# D2D-BOTTOM.net
KiCad netlist of a schematic drawn in EAGLE
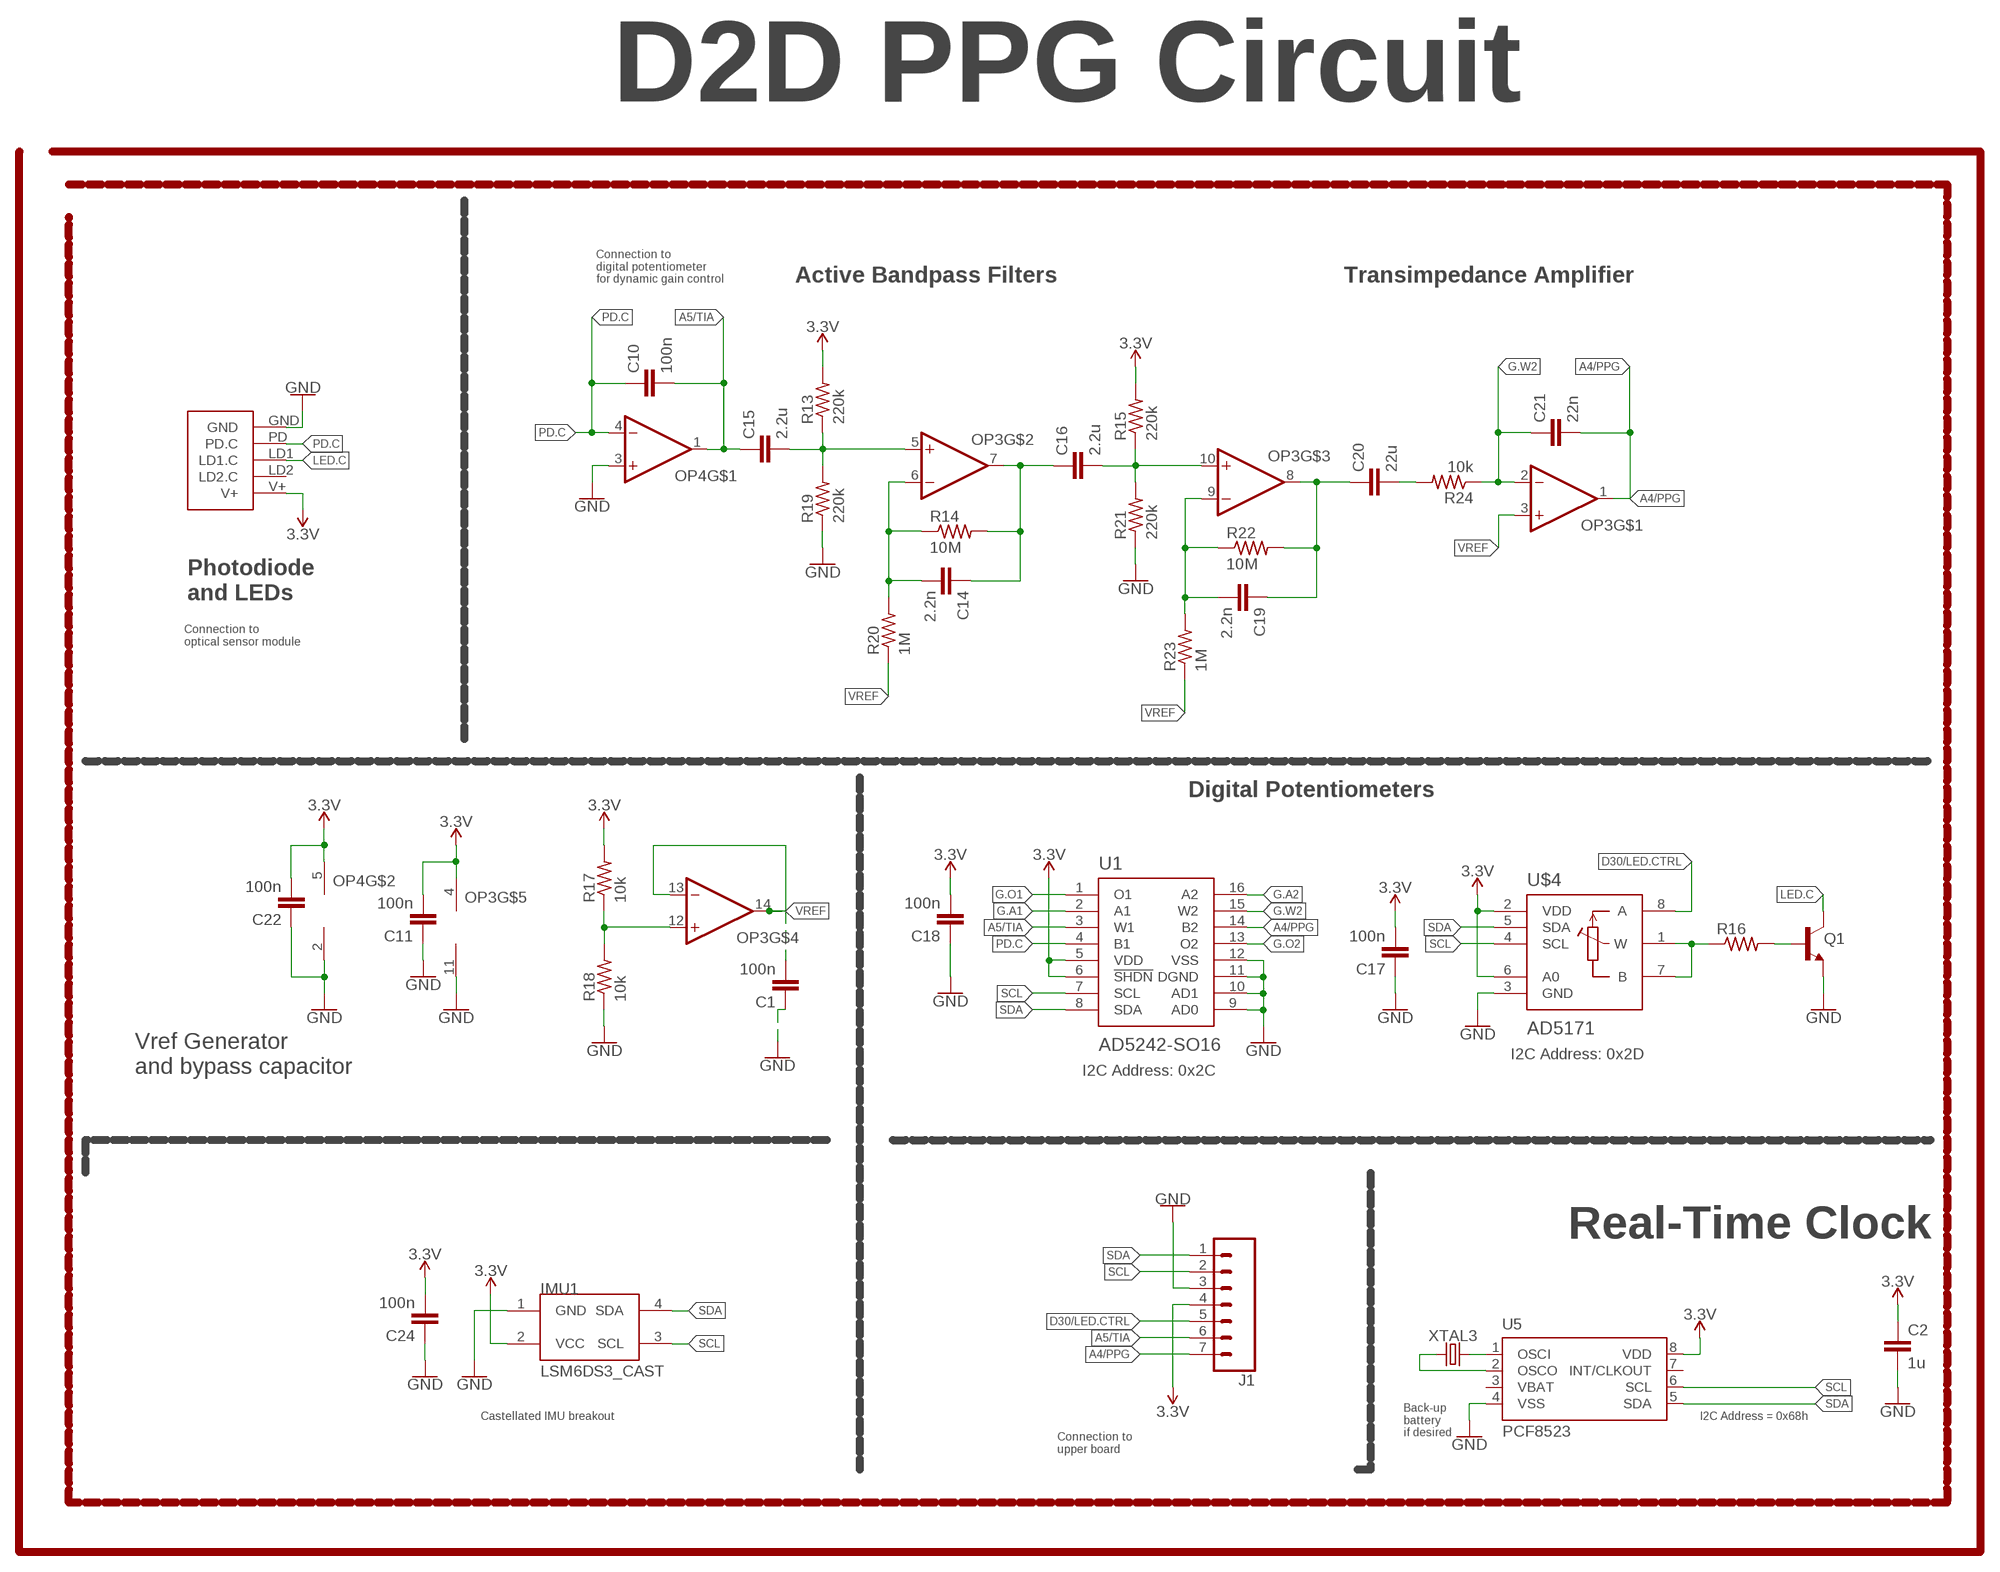
[diagram p0: schematic, sheet 1]

(export (version "E")
  (design (tool "Eeschema 10.0.6"))
  (components
    (comp (ref "C1")
      (value "100n")
      (footprint "eagle-import:C0603")
      (libsource (lib "eagle-import") (part "CAPACITOR0603"))
    )
    (comp (ref "C2")
      (value "1u")
      (footprint "eagle-import:C0603")
      (libsource (lib "eagle-import") (part "CAPACITOR0603"))
    )
    (comp (ref "C10")
      (value "100n")
      (footprint "eagle-import:C0603")
      (libsource (lib "eagle-import") (part "CAPACITOR0603"))
    )
    (comp (ref "C11")
      (value "100n")
      (footprint "eagle-import:C0603")
      (libsource (lib "eagle-import") (part "CAPACITOR0603"))
    )
    (comp (ref "C14")
      (value "2.2n")
      (footprint "eagle-import:C0603")
      (libsource (lib "eagle-import") (part "CAPACITOR0603"))
    )
    (comp (ref "C15")
      (value "2.2u")
      (footprint "eagle-import:C0603")
      (libsource (lib "eagle-import") (part "CAPACITOR0603"))
    )
    (comp (ref "C16")
      (value "2.2u")
      (footprint "eagle-import:C0603")
      (libsource (lib "eagle-import") (part "CAPACITOR0603"))
    )
    (comp (ref "C17")
      (value "100n")
      (footprint "eagle-import:C0603")
      (libsource (lib "eagle-import") (part "CAPACITOR0603"))
    )
    (comp (ref "C18")
      (value "100n")
      (footprint "eagle-import:C0603")
      (libsource (lib "eagle-import") (part "CAPACITOR0603"))
    )
    (comp (ref "C19")
      (value "2.2n")
      (footprint "eagle-import:C0603")
      (libsource (lib "eagle-import") (part "CAPACITOR0603"))
    )
    (comp (ref "C20")
      (value "22u")
      (footprint "eagle-import:C0603")
      (libsource (lib "eagle-import") (part "CAPACITOR0603"))
    )
    (comp (ref "C21")
      (value "22n")
      (footprint "eagle-import:C0603")
      (libsource (lib "eagle-import") (part "CAPACITOR0603"))
    )
    (comp (ref "C22")
      (value "100n")
      (footprint "eagle-import:C0603")
      (libsource (lib "eagle-import") (part "CAPACITOR0603"))
    )
    (comp (ref "C24")
      (value "100n")
      (footprint "eagle-import:C0603")
      (libsource (lib "eagle-import") (part "CAPACITOR0603"))
    )
    (comp (ref "IMU1")
      (value "LSM6DS3_CAST")
      (footprint "eagle-import:LSM6DS3_CAST")
      (libsource (lib "eagle-import") (part "LSM6DS3_CAST"))
    )
    (comp (ref "J1")
      (value "CONN_07-1.27MM")
      (footprint "eagle-import:1X07_1.27MM")
      (libsource (lib "eagle-import") (part "CONN_07-1.27MM"))
    )
    (comp (ref "OP3")
      (value "OP-QUAD-SO14")
      (footprint "eagle-import:SO14")
      (libsource (lib "eagle-import") (part "OP-QUAD-SO14"))
    )
    (comp (ref "OP4")
      (value "OP-SINGLEOT")
      (footprint "eagle-import:SOT23-5")
      (libsource (lib "eagle-import") (part "OP-SINGLEOT"))
    )
    (comp (ref "Q1")
      (value "NPN-GENERIC")
      (footprint "eagle-import:SOT23-3")
      (libsource (lib "eagle-import") (part "NPN-GENERIC"))
    )
    (comp (ref "R13")
      (value "220k")
      (footprint "eagle-import:R0603")
      (libsource (lib "eagle-import") (part "RESISTOR0603"))
    )
    (comp (ref "R14")
      (value "10M")
      (footprint "eagle-import:R0603")
      (libsource (lib "eagle-import") (part "RESISTOR0603"))
    )
    (comp (ref "R15")
      (value "220k")
      (footprint "eagle-import:R0603")
      (libsource (lib "eagle-import") (part "RESISTOR0603"))
    )
    (comp (ref "R16")
      (value "RESISTOR0603")
      (footprint "eagle-import:R0603")
      (libsource (lib "eagle-import") (part "RESISTOR0603"))
    )
    (comp (ref "R17")
      (value "10k")
      (footprint "eagle-import:R0402")
      (libsource (lib "eagle-import") (part "RESISTOR0402"))
    )
    (comp (ref "R18")
      (value "10k")
      (footprint "eagle-import:R0402")
      (libsource (lib "eagle-import") (part "RESISTOR0402"))
    )
    (comp (ref "R19")
      (value "220k")
      (footprint "eagle-import:R0603")
      (libsource (lib "eagle-import") (part "RESISTOR0603"))
    )
    (comp (ref "R20")
      (value "1M")
      (footprint "eagle-import:R0603")
      (libsource (lib "eagle-import") (part "RESISTOR0603"))
    )
    (comp (ref "R21")
      (value "220k")
      (footprint "eagle-import:R0603")
      (libsource (lib "eagle-import") (part "RESISTOR0603"))
    )
    (comp (ref "R22")
      (value "10M")
      (footprint "eagle-import:R0603")
      (libsource (lib "eagle-import") (part "RESISTOR0603"))
    )
    (comp (ref "R23")
      (value "1M")
      (footprint "eagle-import:R0603")
      (libsource (lib "eagle-import") (part "RESISTOR0603"))
    )
    (comp (ref "R24")
      (value "10k")
      (footprint "eagle-import:R0603")
      (libsource (lib "eagle-import") (part "RESISTOR0603"))
    )
    (comp (ref "U$3")
      (value "PPG.MODULE.2")
      (footprint "eagle-import:PPG.MODULE.2")
      (libsource (lib "eagle-import") (part "PPG.MODULE.2"))
    )
    (comp (ref "U$4")
      (value "AD5171")
      (footprint "eagle-import:SOT-23-8")
      (libsource (lib "eagle-import") (part "AD5171"))
    )
    (comp (ref "U1")
      (value "AD5242-SO16")
      (footprint "eagle-import:SO16")
      (libsource (lib "eagle-import") (part "AD5242-SO16"))
    )
    (comp (ref "U5")
      (value "PCF8523")
      (footprint "eagle-import:SO8")
      (libsource (lib "eagle-import") (part "PCF8523"))
    )
    (comp (ref "XTAL3")
      (value "32.7680kHz")
      (footprint "eagle-import:2-SMD.NOLEAD.2.0MMTO1.2MM")
      (fields (field (name "FREQ") "32.7680KHZ"))
      (libsource (lib "eagle-import") (part "CRYSTALECS-.327-12.5-12-C-TR"))
    )
  )
  (nets
    (net (code "1") (name "/VBAT") (class "Default")
      (node (ref "U5") (pin "3") (pinfunction "VBAT_3") (pintype "power_in"))
    )
    (net (code "2") (name "3.3V") (class "Default")
      (node (ref "C11") (pin "2") (pinfunction "2_2") (pintype "passive"))
      (node (ref "C17") (pin "2") (pinfunction "2_2") (pintype "passive"))
      (node (ref "C18") (pin "2") (pinfunction "2_2") (pintype "passive"))
      (node (ref "C2") (pin "1") (pinfunction "1_1") (pintype "passive"))
      (node (ref "C22") (pin "2") (pinfunction "2_2") (pintype "passive"))
      (node (ref "C24") (pin "2") (pinfunction "2_2") (pintype "passive"))
      (node (ref "IMU1") (pin "2") (pinfunction "VCC_2") (pintype "bidirectional"))
      (node (ref "J1") (pin "4") (pinfunction "4_4") (pintype "passive"))
      (node (ref "OP3") (pin "4") (pinfunction "V+_4") (pintype "power_in"))
      (node (ref "OP4") (pin "5") (pinfunction "V+_5") (pintype "power_in"))
      (node (ref "R13") (pin "2") (pinfunction "2_2") (pintype "passive"))
      (node (ref "R15") (pin "2") (pinfunction "2_2") (pintype "passive"))
      (node (ref "R17") (pin "2") (pinfunction "2_2") (pintype "passive"))
      (node (ref "U$3") (pin "V+") (pinfunction "V+_V+") (pintype "bidirectional"))
      (node (ref "U$4") (pin "2") (pinfunction "VDD_2") (pintype "bidirectional"))
      (node (ref "U$4") (pin "6") (pinfunction "A0_6") (pintype "bidirectional"))
      (node (ref "U1") (pin "5") (pinfunction "VDD_5") (pintype "bidirectional"))
      (node (ref "U1") (pin "6") (pinfunction "~{SHDN}_6") (pintype "bidirectional"))
      (node (ref "U5") (pin "8") (pinfunction "VDD_8") (pintype "power_in"))
    )
    (net (code "3") (name "A4{slash}PPG") (class "Default")
      (node (ref "C21") (pin "2") (pinfunction "2_2") (pintype "passive"))
      (node (ref "J1") (pin "7") (pinfunction "7_7") (pintype "passive"))
      (node (ref "OP3") (pin "1") (pinfunction "OUT_1") (pintype "output"))
      (node (ref "U1") (pin "14") (pinfunction "B2_14") (pintype "bidirectional"))
    )
    (net (code "4") (name "A5{slash}TIA") (class "Default")
      (node (ref "C10") (pin "2") (pinfunction "2_2") (pintype "passive"))
      (node (ref "C15") (pin "1") (pinfunction "1_1") (pintype "passive"))
      (node (ref "J1") (pin "6") (pinfunction "6_6") (pintype "passive"))
      (node (ref "OP4") (pin "1") (pinfunction "OUT_1") (pintype "output"))
      (node (ref "U1") (pin "3") (pinfunction "W1_3") (pintype "bidirectional"))
    )
    (net (code "5") (name "D30{slash}LED.CTRL") (class "Default")
      (node (ref "J1") (pin "5") (pinfunction "5_5") (pintype "passive"))
      (node (ref "U$4") (pin "8") (pinfunction "A_8") (pintype "bidirectional"))
    )
    (net (code "6") (name "G.A1") (class "Default")
      (node (ref "U1") (pin "2") (pinfunction "A1_2") (pintype "bidirectional"))
    )
    (net (code "7") (name "G.A2") (class "Default")
      (node (ref "U1") (pin "16") (pinfunction "A2_16") (pintype "bidirectional"))
    )
    (net (code "8") (name "G.O1") (class "Default")
      (node (ref "U1") (pin "1") (pinfunction "O1_1") (pintype "bidirectional"))
    )
    (net (code "9") (name "G.O2") (class "Default")
      (node (ref "U1") (pin "13") (pinfunction "O2_13") (pintype "bidirectional"))
    )
    (net (code "10") (name "G.W2") (class "Default")
      (node (ref "C21") (pin "1") (pinfunction "1_1") (pintype "passive"))
      (node (ref "OP3") (pin "2") (pinfunction "-IN_2") (pintype "input"))
      (node (ref "R24") (pin "1") (pinfunction "1_1") (pintype "passive"))
      (node (ref "U1") (pin "15") (pinfunction "W2_15") (pintype "bidirectional"))
    )
    (net (code "11") (name "GND") (class "Default")
      (node (ref "C1") (pin "1") (pinfunction "1_1") (pintype "passive"))
      (node (ref "C11") (pin "1") (pinfunction "1_1") (pintype "passive"))
      (node (ref "C17") (pin "1") (pinfunction "1_1") (pintype "passive"))
      (node (ref "C18") (pin "1") (pinfunction "1_1") (pintype "passive"))
      (node (ref "C2") (pin "2") (pinfunction "2_2") (pintype "passive"))
      (node (ref "C22") (pin "1") (pinfunction "1_1") (pintype "passive"))
      (node (ref "C24") (pin "1") (pinfunction "1_1") (pintype "passive"))
      (node (ref "IMU1") (pin "1") (pinfunction "GND_1") (pintype "bidirectional"))
      (node (ref "J1") (pin "3") (pinfunction "3_3") (pintype "passive"))
      (node (ref "OP3") (pin "11") (pinfunction "V-_11") (pintype "power_in"))
      (node (ref "OP4") (pin "2") (pinfunction "V-_2") (pintype "power_in"))
      (node (ref "OP4") (pin "3") (pinfunction "+IN_3") (pintype "input"))
      (node (ref "Q1") (pin "2") (pinfunction "E_2") (pintype "passive"))
      (node (ref "R18") (pin "1") (pinfunction "1_1") (pintype "passive"))
      (node (ref "R19") (pin "1") (pinfunction "1_1") (pintype "passive"))
      (node (ref "R21") (pin "1") (pinfunction "1_1") (pintype "passive"))
      (node (ref "U$3") (pin "GND") (pinfunction "GND_GND") (pintype "bidirectional"))
      (node (ref "U$4") (pin "3") (pinfunction "GND_3") (pintype "bidirectional"))
      (node (ref "U1") (pin "10") (pinfunction "AD1_10") (pintype "bidirectional"))
      (node (ref "U1") (pin "11") (pinfunction "DGND_11") (pintype "bidirectional"))
      (node (ref "U1") (pin "12") (pinfunction "VSS_12") (pintype "bidirectional"))
      (node (ref "U1") (pin "9") (pinfunction "AD0_9") (pintype "bidirectional"))
      (node (ref "U5") (pin "4") (pinfunction "VSS_4") (pintype "power_in"))
    )
    (net (code "12") (name "LED.C") (class "Default")
      (node (ref "Q1") (pin "3") (pinfunction "C_3") (pintype "passive"))
      (node (ref "U$3") (pin "LD1") (pinfunction "LD1.C_LD1") (pintype "bidirectional"))
    )
    (net (code "13") (name "Net-(C20-Pad2)") (class "Default")
      (node (ref "C20") (pin "2") (pinfunction "2_2") (pintype "passive"))
      (node (ref "R24") (pin "2") (pinfunction "2_2") (pintype "passive"))
    )
    (net (code "14") (name "Net-(OP3B-+IN)") (class "Default")
      (node (ref "C15") (pin "2") (pinfunction "2_2") (pintype "passive"))
      (node (ref "OP3") (pin "5") (pinfunction "+IN_5") (pintype "input"))
      (node (ref "R13") (pin "1") (pinfunction "1_1") (pintype "passive"))
      (node (ref "R19") (pin "2") (pinfunction "2_2") (pintype "passive"))
    )
    (net (code "15") (name "Net-(OP3B--IN)") (class "Default")
      (node (ref "C14") (pin "2") (pinfunction "2_2") (pintype "passive"))
      (node (ref "OP3") (pin "6") (pinfunction "-IN_6") (pintype "input"))
      (node (ref "R14") (pin "1") (pinfunction "1_1") (pintype "passive"))
      (node (ref "R20") (pin "2") (pinfunction "2_2") (pintype "passive"))
    )
    (net (code "16") (name "Net-(OP3B-OUT)") (class "Default")
      (node (ref "C14") (pin "1") (pinfunction "1_1") (pintype "passive"))
      (node (ref "C16") (pin "1") (pinfunction "1_1") (pintype "passive"))
      (node (ref "OP3") (pin "7") (pinfunction "OUT_7") (pintype "output"))
      (node (ref "R14") (pin "2") (pinfunction "2_2") (pintype "passive"))
    )
    (net (code "17") (name "Net-(OP3C-+IN)") (class "Default")
      (node (ref "C16") (pin "2") (pinfunction "2_2") (pintype "passive"))
      (node (ref "OP3") (pin "10") (pinfunction "+IN_10") (pintype "input"))
      (node (ref "R15") (pin "1") (pinfunction "1_1") (pintype "passive"))
      (node (ref "R21") (pin "2") (pinfunction "2_2") (pintype "passive"))
    )
    (net (code "18") (name "Net-(OP3C--IN)") (class "Default")
      (node (ref "C19") (pin "2") (pinfunction "2_2") (pintype "passive"))
      (node (ref "OP3") (pin "9") (pinfunction "-IN_9") (pintype "input"))
      (node (ref "R22") (pin "1") (pinfunction "1_1") (pintype "passive"))
      (node (ref "R23") (pin "2") (pinfunction "2_2") (pintype "passive"))
    )
    (net (code "19") (name "Net-(OP3C-OUT)") (class "Default")
      (node (ref "C19") (pin "1") (pinfunction "1_1") (pintype "passive"))
      (node (ref "C20") (pin "1") (pinfunction "1_1") (pintype "passive"))
      (node (ref "OP3") (pin "8") (pinfunction "OUT_8") (pintype "output"))
      (node (ref "R22") (pin "2") (pinfunction "2_2") (pintype "passive"))
    )
    (net (code "20") (name "Net-(OP3D-+IN)") (class "Default")
      (node (ref "OP3") (pin "12") (pinfunction "+IN_12") (pintype "input"))
      (node (ref "R17") (pin "1") (pinfunction "1_1") (pintype "passive"))
      (node (ref "R18") (pin "2") (pinfunction "2_2") (pintype "passive"))
    )
    (net (code "21") (name "Net-(Q1-B)") (class "Default")
      (node (ref "Q1") (pin "1") (pinfunction "B_1") (pintype "passive"))
      (node (ref "R16") (pin "2") (pinfunction "2_2") (pintype "passive"))
    )
    (net (code "22") (name "Net-(U$4-B)") (class "Default")
      (node (ref "R16") (pin "1") (pinfunction "1_1") (pintype "passive"))
      (node (ref "U$4") (pin "1") (pinfunction "W_1") (pintype "bidirectional"))
      (node (ref "U$4") (pin "7") (pinfunction "B_7") (pintype "bidirectional"))
    )
    (net (code "23") (name "Net-(U5-OSCI)") (class "Default")
      (node (ref "U5") (pin "1") (pinfunction "OSCI_1") (pintype "bidirectional"))
      (node (ref "XTAL3") (pin "P$2") (pinfunction "2_P$2") (pintype "passive"))
    )
    (net (code "24") (name "Net-(U5-OSCO)") (class "Default")
      (node (ref "U5") (pin "2") (pinfunction "OSCO_2") (pintype "bidirectional"))
      (node (ref "XTAL3") (pin "P$1") (pinfunction "1_P$1") (pintype "passive"))
    )
    (net (code "25") (name "PD.C") (class "Default")
      (node (ref "C10") (pin "1") (pinfunction "1_1") (pintype "passive"))
      (node (ref "OP4") (pin "4") (pinfunction "-IN_4") (pintype "input"))
      (node (ref "U$3") (pin "PD") (pinfunction "PD.C_PD") (pintype "bidirectional"))
      (node (ref "U1") (pin "4") (pinfunction "B1_4") (pintype "bidirectional"))
    )
    (net (code "26") (name "SCL") (class "Default")
      (node (ref "IMU1") (pin "3") (pinfunction "SCL_3") (pintype "bidirectional"))
      (node (ref "J1") (pin "2") (pinfunction "2_2") (pintype "passive"))
      (node (ref "U$4") (pin "4") (pinfunction "SCL_4") (pintype "bidirectional"))
      (node (ref "U1") (pin "7") (pinfunction "SCL_7") (pintype "bidirectional"))
      (node (ref "U5") (pin "6") (pinfunction "SCL_6") (pintype "bidirectional"))
    )
    (net (code "27") (name "SDA") (class "Default")
      (node (ref "IMU1") (pin "4") (pinfunction "SDA_4") (pintype "bidirectional"))
      (node (ref "J1") (pin "1") (pinfunction "1_1") (pintype "passive"))
      (node (ref "U$4") (pin "5") (pinfunction "SDA_5") (pintype "bidirectional"))
      (node (ref "U1") (pin "8") (pinfunction "SDA_8") (pintype "bidirectional"))
      (node (ref "U5") (pin "5") (pinfunction "SDA_5") (pintype "bidirectional"))
    )
    (net (code "28") (name "VREF") (class "Default")
      (node (ref "C1") (pin "2") (pinfunction "2_2") (pintype "passive"))
      (node (ref "OP3") (pin "13") (pinfunction "-IN_13") (pintype "input"))
      (node (ref "OP3") (pin "14") (pinfunction "OUT_14") (pintype "output"))
      (node (ref "OP3") (pin "3") (pinfunction "+IN_3") (pintype "input"))
      (node (ref "R20") (pin "1") (pinfunction "1_1") (pintype "passive"))
      (node (ref "R23") (pin "1") (pinfunction "1_1") (pintype "passive"))
    )
    (net (code "29") (name "unconnected-(U$3-LD2.C-PadLD2)") (class "Default")
      (node (ref "U$3") (pin "LD2") (pinfunction "LD2.C_LD2") (pintype "bidirectional"))
    )
    (net (code "30") (name "unconnected-(U5-INT{slash}CLKOUT-Pad7)") (class "Default")
      (node (ref "U5") (pin "7") (pinfunction "INT/CLKOUT_7") (pintype "bidirectional"))
    )
  )
)
